# RFTuningBoard.net
KiCad netlist of a schematic drawn in Altium Designer
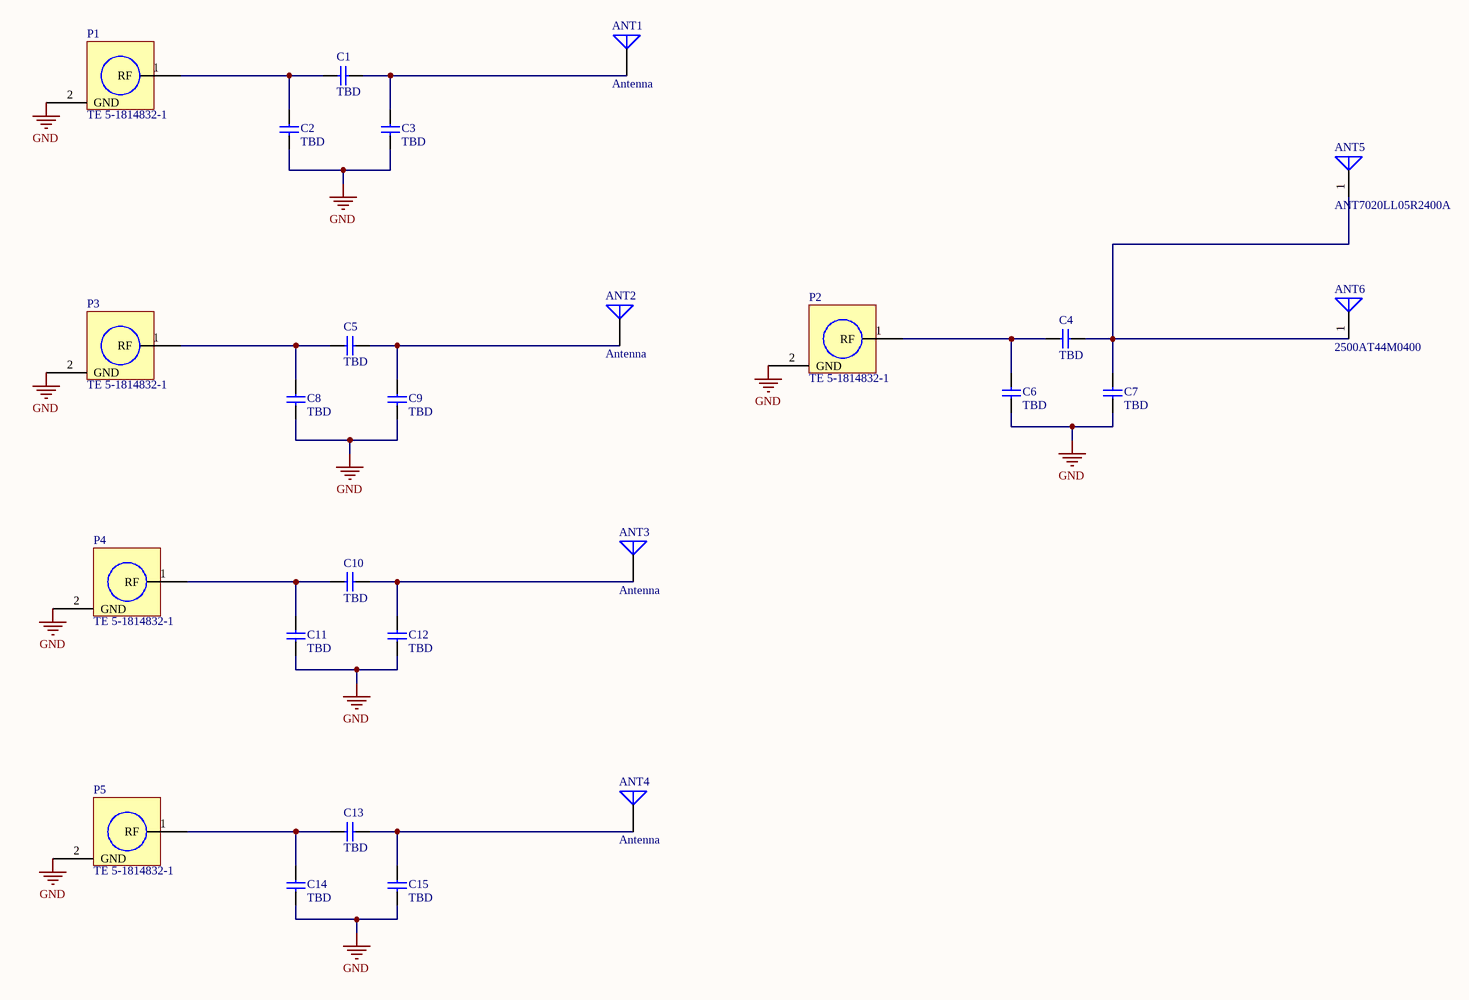
[diagram p0: RFTuningBoard.SchDoc]

(export (version "E")
  (design (tool "Eeschema 10.0.6"))
  (components
    (comp (ref "ANT1")
      (value "Antenna")
      (footprint "ANTENNA_PCB_2.4GHZ")
      (description "Antenna PCB, 2.4GHz, 26.11 mm x 1.27 mm, FR4 60 mils, Er = 4.2")
      (libsource (lib "SmartHalo_Symbols") (part "ANTENNA_PCB_2.4GHz"))
    )
    (comp (ref "ANT2")
      (value "Antenna")
      (footprint "ANT_2.4GHZ_FR408_4L_CMIFA")
      (description "Antenna PCB, 2.4GHz")
      (libsource (lib "SmartHalo") (part "ANTENNA_PCB_2.4GHz_2PINS"))
    )
    (comp (ref "ANT3")
      (value "Antenna")
      (footprint "ANT_2.4GHZ_FR408_4L_Meander")
      (description "Antenna PCB, 2.4GHz, 26.11 mm x 1.27 mm, FR4 60 mils, Er = 4.2")
      (libsource (lib "SmartHalo_Symbols") (part "ANTENNA_PCB_2.4GHz"))
    )
    (comp (ref "ANT4")
      (value "Antenna")
      (footprint "ANT_2.4GHZ_FR408_4L_TIFA")
      (description "Antenna PCB, 2.4GHz")
      (libsource (lib "SmartHalo") (part "ANTENNA_PCB_2.4GHz_2PINS"))
    )
    (comp (ref "ANT5")
      (value "ANT7020LL05R2400A")
      (footprint "ANT7020LL05R2400A")
      (description "CHIP ANTENNA, 2.45GHz, 7 x 2 mm body")
      (fields (field (name "MANUFACTURER") "Yageo"))
      (libsource (lib "SmartHalo") (part "ANT7020LL05R2400A"))
    )
    (comp (ref "ANT6")
      (value "2500AT44M0400")
      (footprint "2500AT44M0400")
      (description "CHIP ANTENNA, 2.45GHz, 8 x 1 mm body")
      (fields (field (name "MANUFACTURER") "Johanson Technology"))
      (libsource (lib "SmartHalo") (part "2500AT44M0400"))
    )
    (comp (ref "C1")
      (value "TBD")
      (footprint "SmartHalo:CAPC0603(1608)100_N")
      (description "Chip Cap 0603 X7R 10%")
      (libsource (lib "SmartHalo") (part "CAP0603"))
    )
    (comp (ref "C2")
      (value "TBD")
      (footprint "SmartHalo:CAPC0603(1608)100_N")
      (description "Chip Cap 0603 X7R 10%")
      (libsource (lib "SmartHalo") (part "CAP0603"))
    )
    (comp (ref "C3")
      (value "TBD")
      (footprint "SmartHalo:CAPC0603(1608)100_N")
      (description "Chip Cap 0603 X7R 10%")
      (libsource (lib "SmartHalo") (part "CAP0603"))
    )
    (comp (ref "C4")
      (value "TBD")
      (footprint "SmartHalo:CAPC0603(1608)100_N")
      (description "Chip Cap 0603 X7R 10%")
      (libsource (lib "SmartHalo") (part "CAP0603"))
    )
    (comp (ref "C5")
      (value "TBD")
      (footprint "SmartHalo:CAPC0603(1608)100_N")
      (description "Chip Cap 0603 X7R 10%")
      (libsource (lib "SmartHalo") (part "CAP0603"))
    )
    (comp (ref "C6")
      (value "TBD")
      (footprint "SmartHalo:CAPC0603(1608)100_N")
      (description "Chip Cap 0603 X7R 10%")
      (libsource (lib "SmartHalo") (part "CAP0603"))
    )
    (comp (ref "C7")
      (value "TBD")
      (footprint "SmartHalo:CAPC0603(1608)100_N")
      (description "Chip Cap 0603 X7R 10%")
      (libsource (lib "SmartHalo") (part "CAP0603"))
    )
    (comp (ref "C8")
      (value "TBD")
      (footprint "SmartHalo:CAPC0603(1608)100_N")
      (description "Chip Cap 0603 X7R 10%")
      (libsource (lib "SmartHalo") (part "CAP0603"))
    )
    (comp (ref "C9")
      (value "TBD")
      (footprint "SmartHalo:CAPC0603(1608)100_N")
      (description "Chip Cap 0603 X7R 10%")
      (libsource (lib "SmartHalo") (part "CAP0603"))
    )
    (comp (ref "C10")
      (value "TBD")
      (footprint "SmartHalo:CAPC0603(1608)100_N")
      (description "Chip Cap 0603 X7R 10%")
      (libsource (lib "SmartHalo") (part "CAP0603"))
    )
    (comp (ref "C11")
      (value "TBD")
      (footprint "SmartHalo:CAPC0603(1608)100_N")
      (description "Chip Cap 0603 X7R 10%")
      (libsource (lib "SmartHalo") (part "CAP0603"))
    )
    (comp (ref "C12")
      (value "TBD")
      (footprint "SmartHalo:CAPC0603(1608)100_N")
      (description "Chip Cap 0603 X7R 10%")
      (libsource (lib "SmartHalo") (part "CAP0603"))
    )
    (comp (ref "C13")
      (value "TBD")
      (footprint "SmartHalo:CAPC0603(1608)100_N")
      (description "Chip Cap 0603 X7R 10%")
      (libsource (lib "SmartHalo") (part "CAP0603"))
    )
    (comp (ref "C14")
      (value "TBD")
      (footprint "SmartHalo:CAPC0603(1608)100_N")
      (description "Chip Cap 0603 X7R 10%")
      (libsource (lib "SmartHalo") (part "CAP0603"))
    )
    (comp (ref "C15")
      (value "TBD")
      (footprint "SmartHalo:CAPC0603(1608)100_N")
      (description "Chip Cap 0603 X7R 10%")
      (libsource (lib "SmartHalo") (part "CAP0603"))
    )
    (comp (ref "P1")
      (value "TE 5-1814832-1")
      (footprint "TE_SMA_TH")
      (description "CONN SMA JACK STR 50 OHM PCB")
      (fields (field (name "MANUFACTURER") "TE Connectivity"))
      (libsource (lib "SmartHalo") (part "5-1814832-1"))
    )
    (comp (ref "P2")
      (value "TE 5-1814832-1")
      (footprint "TE_SMA_TH")
      (description "CONN SMA JACK STR 50 OHM PCB")
      (fields (field (name "MANUFACTURER") "TE Connectivity"))
      (libsource (lib "SmartHalo") (part "5-1814832-1"))
    )
    (comp (ref "P3")
      (value "TE 5-1814832-1")
      (footprint "TE_SMA_TH")
      (description "CONN SMA JACK STR 50 OHM PCB")
      (fields (field (name "MANUFACTURER") "TE Connectivity"))
      (libsource (lib "SmartHalo") (part "5-1814832-1"))
    )
    (comp (ref "P4")
      (value "TE 5-1814832-1")
      (footprint "TE_SMA_TH")
      (description "CONN SMA JACK STR 50 OHM PCB")
      (fields (field (name "MANUFACTURER") "TE Connectivity"))
      (libsource (lib "SmartHalo") (part "5-1814832-1"))
    )
    (comp (ref "P5")
      (value "TE 5-1814832-1")
      (footprint "TE_SMA_TH")
      (description "CONN SMA JACK STR 50 OHM PCB")
      (fields (field (name "MANUFACTURER") "TE Connectivity"))
      (libsource (lib "SmartHalo") (part "5-1814832-1"))
    )
  )
  (nets
    (net (code "1") (name "GND") (class "Default")
      (node (ref "ANT2") (pin "2") (pinfunction "GND_2") (pintype "power_in"))
      (node (ref "ANT4") (pin "2") (pinfunction "GND_2") (pintype "power_in"))
      (node (ref "C11") (pin "2") (pinfunction "2_2") (pintype "passive"))
      (node (ref "C12") (pin "2") (pinfunction "2_2") (pintype "passive"))
      (node (ref "C14") (pin "2") (pinfunction "2_2") (pintype "passive"))
      (node (ref "C15") (pin "2") (pinfunction "2_2") (pintype "passive"))
      (node (ref "C2") (pin "2") (pinfunction "2_2") (pintype "passive"))
      (node (ref "C3") (pin "2") (pinfunction "2_2") (pintype "passive"))
      (node (ref "C6") (pin "2") (pinfunction "2_2") (pintype "passive"))
      (node (ref "C7") (pin "2") (pinfunction "2_2") (pintype "passive"))
      (node (ref "C8") (pin "2") (pinfunction "2_2") (pintype "passive"))
      (node (ref "C9") (pin "2") (pinfunction "2_2") (pintype "passive"))
      (node (ref "P1") (pin "2") (pinfunction "GND_2") (pintype "passive"))
      (node (ref "P2") (pin "2") (pinfunction "GND_2") (pintype "passive"))
      (node (ref "P3") (pin "2") (pinfunction "GND_2") (pintype "passive"))
      (node (ref "P4") (pin "2") (pinfunction "GND_2") (pintype "passive"))
      (node (ref "P5") (pin "2") (pinfunction "GND_2") (pintype "passive"))
    )
    (net (code "2") (name "Net-(ANT1-Feed)") (class "Default")
      (node (ref "ANT1") (pin "1") (pinfunction "Feed_1") (pintype "passive"))
      (node (ref "C1") (pin "2") (pinfunction "2_2") (pintype "passive"))
      (node (ref "C3") (pin "1") (pinfunction "1_1") (pintype "passive"))
    )
    (net (code "3") (name "Net-(ANT2-Feed)") (class "Default")
      (node (ref "ANT2") (pin "1") (pinfunction "Feed_1") (pintype "passive"))
      (node (ref "C5") (pin "2") (pinfunction "2_2") (pintype "passive"))
      (node (ref "C9") (pin "1") (pinfunction "1_1") (pintype "passive"))
    )
    (net (code "4") (name "Net-(ANT3-Feed)") (class "Default")
      (node (ref "ANT3") (pin "1") (pinfunction "Feed_1") (pintype "passive"))
      (node (ref "C10") (pin "2") (pinfunction "2_2") (pintype "passive"))
      (node (ref "C12") (pin "1") (pinfunction "1_1") (pintype "passive"))
    )
    (net (code "5") (name "Net-(ANT4-Feed)") (class "Default")
      (node (ref "ANT4") (pin "1") (pinfunction "Feed_1") (pintype "passive"))
      (node (ref "C13") (pin "2") (pinfunction "2_2") (pintype "passive"))
      (node (ref "C15") (pin "1") (pinfunction "1_1") (pintype "passive"))
    )
    (net (code "6") (name "Net-(ANT5-Feed)") (class "Default")
      (node (ref "ANT5") (pin "1") (pinfunction "Feed_1") (pintype "passive"))
      (node (ref "ANT6") (pin "1") (pinfunction "Feed_1") (pintype "passive"))
      (node (ref "C4") (pin "2") (pinfunction "2_2") (pintype "passive"))
      (node (ref "C7") (pin "1") (pinfunction "1_1") (pintype "passive"))
    )
    (net (code "7") (name "Net-(P1-RF)") (class "Default")
      (node (ref "C1") (pin "1") (pinfunction "1_1") (pintype "passive"))
      (node (ref "C2") (pin "1") (pinfunction "1_1") (pintype "passive"))
      (node (ref "P1") (pin "1") (pinfunction "RF_1") (pintype "passive"))
    )
    (net (code "8") (name "Net-(P2-RF)") (class "Default")
      (node (ref "C4") (pin "1") (pinfunction "1_1") (pintype "passive"))
      (node (ref "C6") (pin "1") (pinfunction "1_1") (pintype "passive"))
      (node (ref "P2") (pin "1") (pinfunction "RF_1") (pintype "passive"))
    )
    (net (code "9") (name "Net-(P3-RF)") (class "Default")
      (node (ref "C5") (pin "1") (pinfunction "1_1") (pintype "passive"))
      (node (ref "C8") (pin "1") (pinfunction "1_1") (pintype "passive"))
      (node (ref "P3") (pin "1") (pinfunction "RF_1") (pintype "passive"))
    )
    (net (code "10") (name "Net-(P4-RF)") (class "Default")
      (node (ref "C10") (pin "1") (pinfunction "1_1") (pintype "passive"))
      (node (ref "C11") (pin "1") (pinfunction "1_1") (pintype "passive"))
      (node (ref "P4") (pin "1") (pinfunction "RF_1") (pintype "passive"))
    )
    (net (code "11") (name "Net-(P5-RF)") (class "Default")
      (node (ref "C13") (pin "1") (pinfunction "1_1") (pintype "passive"))
      (node (ref "C14") (pin "1") (pinfunction "1_1") (pintype "passive"))
      (node (ref "P5") (pin "1") (pinfunction "RF_1") (pintype "passive"))
    )
  )
)
